# LB_BIT_o3_RGBLED-v02_rev1.net
KiCad netlist of a schematic drawn in EAGLE
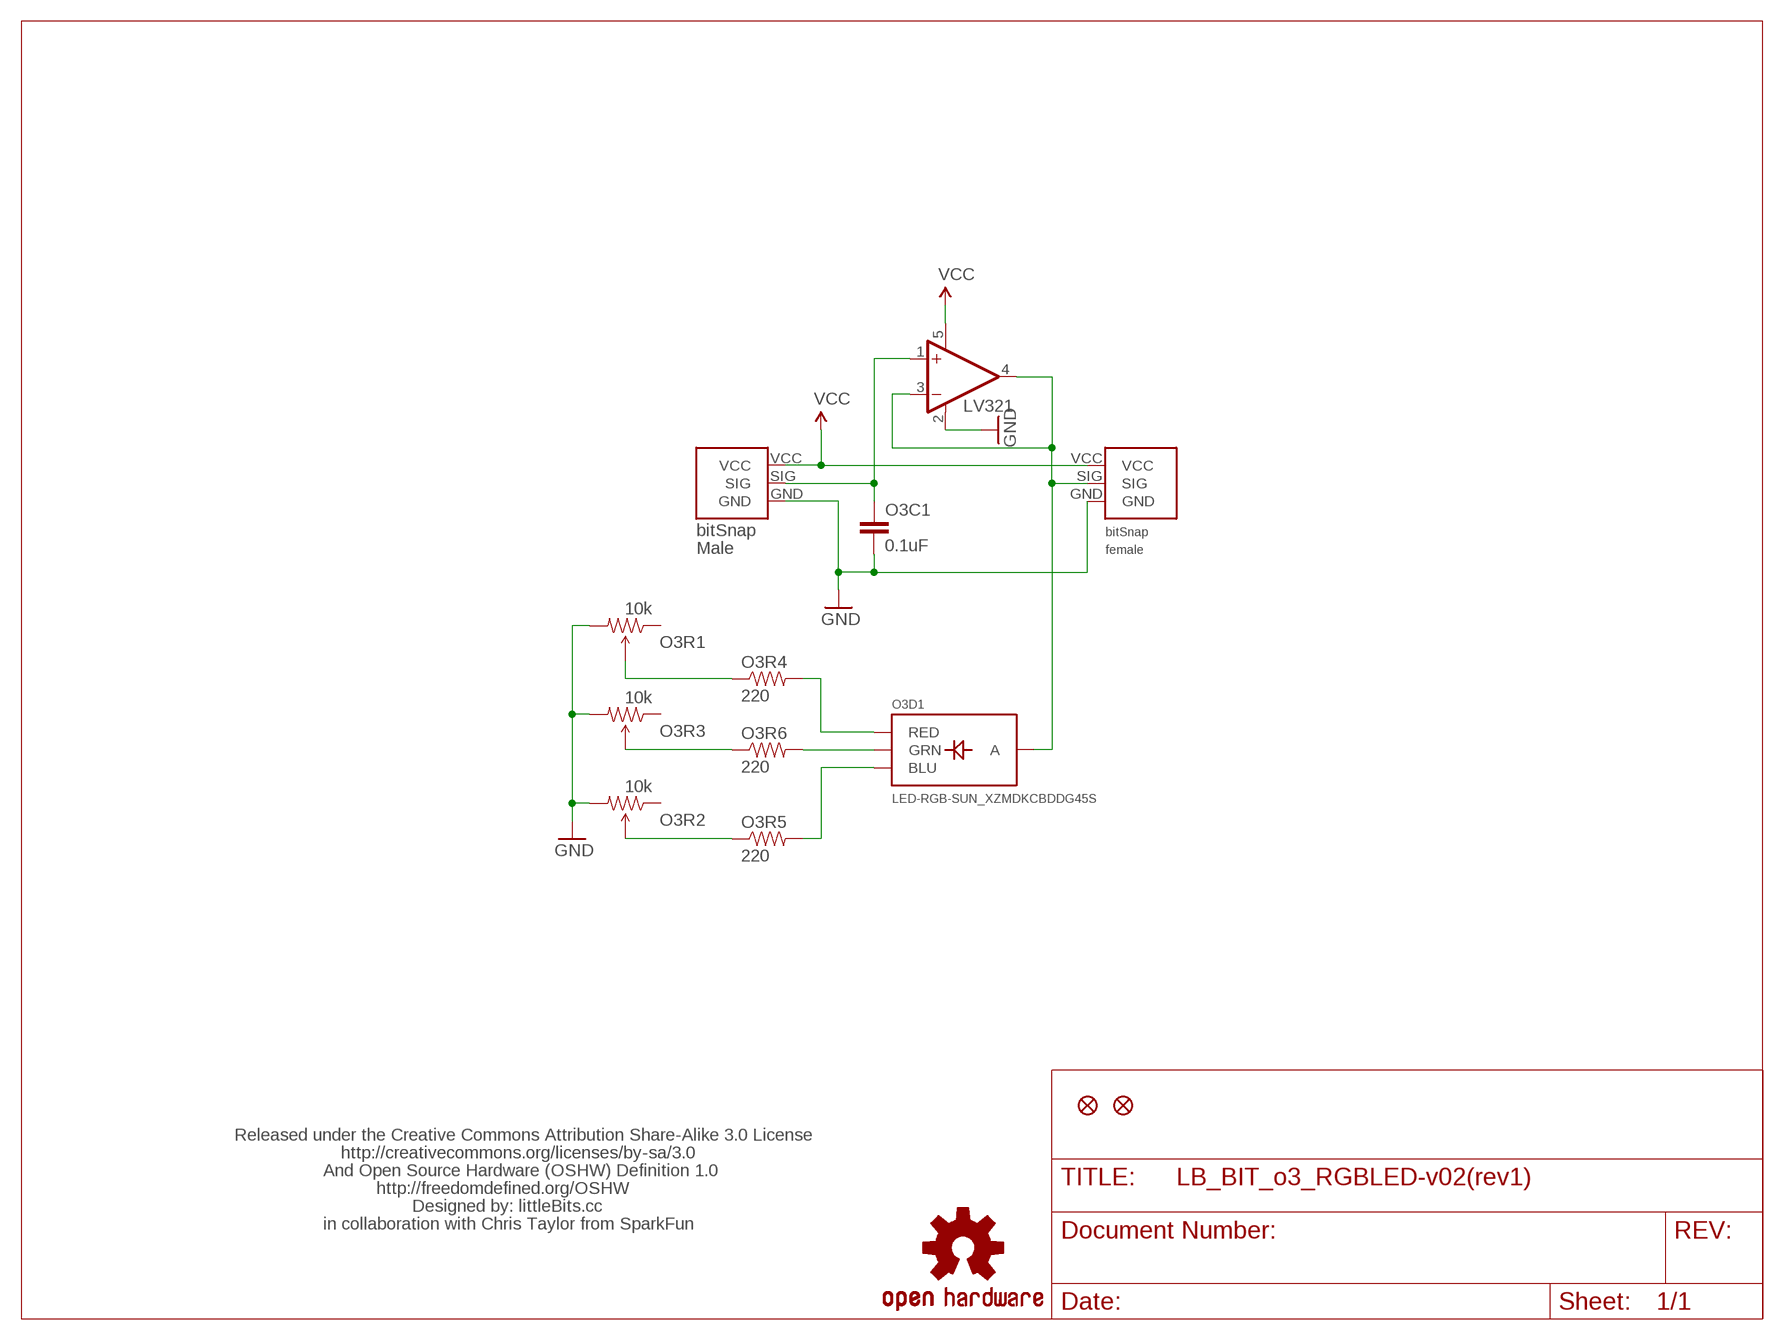
[diagram p0: schematic, sheet 1]

(export (version "E")
  (design (tool "Eeschema 10.0.6"))
  (components
    (comp (ref "JP1")
      (value "FIDUCIAL1X2.5")
      (footprint "eagle-import:FIDUCIAL-1X2.5")
      (libsource (lib "eagle-import") (part "FIDUCIAL1X2.5"))
    )
    (comp (ref "JP2")
      (value "FIDUCIAL1X2.5")
      (footprint "eagle-import:FIDUCIAL-1X2.5")
      (libsource (lib "eagle-import") (part "FIDUCIAL1X2.5"))
    )
    (comp (ref "O3BSF")
      (value "BITSNAP_FEMALE")
      (footprint "eagle-import:BITSNAP_FEMALE")
      (libsource (lib "eagle-import") (part "BITSNAP_FEMALE"))
    )
    (comp (ref "O3BSM")
      (value "BITSNAP_MALE")
      (footprint "eagle-import:BITSNAP_MALE")
      (libsource (lib "eagle-import") (part "BITSNAP_MALE"))
    )
    (comp (ref "O3C1")
      (value "0.1uF")
      (footprint "eagle-import:0603-CAP")
      (libsource (lib "eagle-import") (part "CAP0603-CAP"))
    )
    (comp (ref "O3D1")
      (value "LED-RGB-SUN_XZMDKCBDDG45S")
      (footprint "eagle-import:LED-RGB-SUN_XZMDKCBDDG45S")
      (libsource (lib "eagle-import") (part "LED-RGB-SUN_XZMDKCBDDG45S"))
    )
    (comp (ref "O3R1")
      (value "10k")
      (footprint "eagle-import:TRIMPOT-3MM")
      (libsource (lib "eagle-import") (part "TRIMPOTSMD"))
    )
    (comp (ref "O3R2")
      (value "10k")
      (footprint "eagle-import:TRIMPOT-3MM")
      (libsource (lib "eagle-import") (part "TRIMPOTSMD"))
    )
    (comp (ref "O3R3")
      (value "10k")
      (footprint "eagle-import:TRIMPOT-3MM")
      (libsource (lib "eagle-import") (part "TRIMPOTSMD"))
    )
    (comp (ref "O3R4")
      (value "220")
      (footprint "eagle-import:0603-RES")
      (libsource (lib "eagle-import") (part "RESISTOR0603-RES"))
    )
    (comp (ref "O3R5")
      (value "220")
      (footprint "eagle-import:0603-RES")
      (libsource (lib "eagle-import") (part "RESISTOR0603-RES"))
    )
    (comp (ref "O3R6")
      (value "220")
      (footprint "eagle-import:0603-RES")
      (libsource (lib "eagle-import") (part "RESISTOR0603-RES"))
    )
    (comp (ref "O3U1")
      (value "LV321")
      (footprint "eagle-import:SC70")
      (libsource (lib "eagle-import") (part "LV321"))
    )
    (comp (ref "U$1")
      (value "LB_CREDITS")
      (footprint "eagle-import:OSHWCREDIT")
      (libsource (lib "eagle-import") (part "LB_CREDITS"))
    )
    (comp (ref "U$5")
      (value "OSHW-LOGOL")
      (footprint "eagle-import:OSHW-LOGO-L")
      (libsource (lib "eagle-import") (part "OSHW-LOGOL"))
    )
  )
  (nets
    (net (code "1") (name "GND") (class "Default")
      (node (ref "O3BSF") (pin "GND") (pinfunction "GND_GND") (pintype "bidirectional"))
      (node (ref "O3BSM") (pin "GND") (pinfunction "GND_GND") (pintype "bidirectional"))
      (node (ref "O3C1") (pin "2") (pinfunction "2_2") (pintype "passive"))
      (node (ref "O3R1") (pin "3") (pinfunction "CW_3") (pintype "passive"))
      (node (ref "O3R2") (pin "3") (pinfunction "CW_3") (pintype "passive"))
      (node (ref "O3R3") (pin "3") (pinfunction "CW_3") (pintype "passive"))
      (node (ref "O3U1") (pin "2") (pinfunction "V-_2") (pintype "power_in"))
    )
    (net (code "2") (name "Net-(O3D1-A)") (class "Default")
      (node (ref "O3BSF") (pin "SIG") (pinfunction "SIG_SIG") (pintype "bidirectional"))
      (node (ref "O3D1") (pin "2") (pinfunction "A_2") (pintype "bidirectional"))
      (node (ref "O3U1") (pin "3") (pinfunction "-IN_3") (pintype "input"))
      (node (ref "O3U1") (pin "4") (pinfunction "OUT_4") (pintype "output"))
    )
    (net (code "3") (name "Net-(O3D1-BLU)") (class "Default")
      (node (ref "O3D1") (pin "3") (pinfunction "BLU_3") (pintype "bidirectional"))
      (node (ref "O3R5") (pin "2") (pinfunction "2_2") (pintype "passive"))
    )
    (net (code "4") (name "Net-(O3D1-GRN)") (class "Default")
      (node (ref "O3D1") (pin "4") (pinfunction "GRN_4") (pintype "bidirectional"))
      (node (ref "O3R6") (pin "2") (pinfunction "2_2") (pintype "passive"))
    )
    (net (code "5") (name "Net-(O3D1-RED)") (class "Default")
      (node (ref "O3D1") (pin "1") (pinfunction "RED_1") (pintype "bidirectional"))
      (node (ref "O3R4") (pin "2") (pinfunction "2_2") (pintype "passive"))
    )
    (net (code "6") (name "Net-(O3R1-WIPER)") (class "Default")
      (node (ref "O3R1") (pin "2") (pinfunction "WIPER_2") (pintype "passive"))
      (node (ref "O3R4") (pin "1") (pinfunction "1_1") (pintype "passive"))
    )
    (net (code "7") (name "Net-(O3R2-WIPER)") (class "Default")
      (node (ref "O3R2") (pin "2") (pinfunction "WIPER_2") (pintype "passive"))
      (node (ref "O3R5") (pin "1") (pinfunction "1_1") (pintype "passive"))
    )
    (net (code "8") (name "Net-(O3R3-WIPER)") (class "Default")
      (node (ref "O3R3") (pin "2") (pinfunction "WIPER_2") (pintype "passive"))
      (node (ref "O3R6") (pin "1") (pinfunction "1_1") (pintype "passive"))
    )
    (net (code "9") (name "Net-(O3U1-+IN)") (class "Default")
      (node (ref "O3BSM") (pin "SIG") (pinfunction "SIG_SIG") (pintype "bidirectional"))
      (node (ref "O3C1") (pin "1") (pinfunction "1_1") (pintype "passive"))
      (node (ref "O3U1") (pin "1") (pinfunction "+IN_1") (pintype "input"))
    )
    (net (code "10") (name "VCC") (class "Default")
      (node (ref "O3BSF") (pin "VCC") (pinfunction "VCC_VCC") (pintype "bidirectional"))
      (node (ref "O3BSM") (pin "VCC") (pinfunction "VCC_VCC") (pintype "bidirectional"))
      (node (ref "O3U1") (pin "5") (pinfunction "V+_5") (pintype "power_in"))
    )
    (net (code "11") (name "unconnected-(O3R1-CCW-Pad1)") (class "Default")
      (node (ref "O3R1") (pin "1") (pinfunction "CCW_1") (pintype "passive"))
    )
    (net (code "12") (name "unconnected-(O3R2-CCW-Pad1)") (class "Default")
      (node (ref "O3R2") (pin "1") (pinfunction "CCW_1") (pintype "passive"))
    )
    (net (code "13") (name "unconnected-(O3R3-CCW-Pad1)") (class "Default")
      (node (ref "O3R3") (pin "1") (pinfunction "CCW_1") (pintype "passive"))
    )
  )
)
